# QFN44-2-DIP.net
KiCad netlist of a schematic drawn in EAGLE
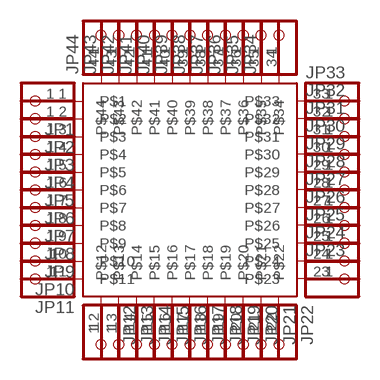
[diagram p0: schematic, sheet 1]

(export (version "E")
  (design (tool "Eeschema 10.0.6"))
  (components
    (comp (ref "JP1")
      (value "PINHD-1X1")
      (footprint "eagle-import:1X01")
      (libsource (lib "eagle-import") (part "PINHD-1X1"))
    )
    (comp (ref "JP2")
      (value "PINHD-1X1")
      (footprint "eagle-import:1X01")
      (libsource (lib "eagle-import") (part "PINHD-1X1"))
    )
    (comp (ref "JP3")
      (value "PINHD-1X1")
      (footprint "eagle-import:1X01")
      (libsource (lib "eagle-import") (part "PINHD-1X1"))
    )
    (comp (ref "JP4")
      (value "PINHD-1X1")
      (footprint "eagle-import:1X01")
      (libsource (lib "eagle-import") (part "PINHD-1X1"))
    )
    (comp (ref "JP5")
      (value "PINHD-1X1")
      (footprint "eagle-import:1X01")
      (libsource (lib "eagle-import") (part "PINHD-1X1"))
    )
    (comp (ref "JP6")
      (value "PINHD-1X1")
      (footprint "eagle-import:1X01")
      (libsource (lib "eagle-import") (part "PINHD-1X1"))
    )
    (comp (ref "JP7")
      (value "PINHD-1X1")
      (footprint "eagle-import:1X01")
      (libsource (lib "eagle-import") (part "PINHD-1X1"))
    )
    (comp (ref "JP8")
      (value "PINHD-1X1")
      (footprint "eagle-import:1X01")
      (libsource (lib "eagle-import") (part "PINHD-1X1"))
    )
    (comp (ref "JP9")
      (value "PINHD-1X1")
      (footprint "eagle-import:1X01")
      (libsource (lib "eagle-import") (part "PINHD-1X1"))
    )
    (comp (ref "JP10")
      (value "PINHD-1X1")
      (footprint "eagle-import:1X01")
      (libsource (lib "eagle-import") (part "PINHD-1X1"))
    )
    (comp (ref "JP11")
      (value "PINHD-1X1")
      (footprint "eagle-import:1X01")
      (libsource (lib "eagle-import") (part "PINHD-1X1"))
    )
    (comp (ref "JP12")
      (value "PINHD-1X1")
      (footprint "eagle-import:1X01")
      (libsource (lib "eagle-import") (part "PINHD-1X1"))
    )
    (comp (ref "JP13")
      (value "PINHD-1X1")
      (footprint "eagle-import:1X01")
      (libsource (lib "eagle-import") (part "PINHD-1X1"))
    )
    (comp (ref "JP14")
      (value "PINHD-1X1")
      (footprint "eagle-import:1X01")
      (libsource (lib "eagle-import") (part "PINHD-1X1"))
    )
    (comp (ref "JP15")
      (value "PINHD-1X1")
      (footprint "eagle-import:1X01")
      (libsource (lib "eagle-import") (part "PINHD-1X1"))
    )
    (comp (ref "JP16")
      (value "PINHD-1X1")
      (footprint "eagle-import:1X01")
      (libsource (lib "eagle-import") (part "PINHD-1X1"))
    )
    (comp (ref "JP17")
      (value "PINHD-1X1")
      (footprint "eagle-import:1X01")
      (libsource (lib "eagle-import") (part "PINHD-1X1"))
    )
    (comp (ref "JP18")
      (value "PINHD-1X1")
      (footprint "eagle-import:1X01")
      (libsource (lib "eagle-import") (part "PINHD-1X1"))
    )
    (comp (ref "JP19")
      (value "PINHD-1X1")
      (footprint "eagle-import:1X01")
      (libsource (lib "eagle-import") (part "PINHD-1X1"))
    )
    (comp (ref "JP20")
      (value "PINHD-1X1")
      (footprint "eagle-import:1X01")
      (libsource (lib "eagle-import") (part "PINHD-1X1"))
    )
    (comp (ref "JP21")
      (value "PINHD-1X1")
      (footprint "eagle-import:1X01")
      (libsource (lib "eagle-import") (part "PINHD-1X1"))
    )
    (comp (ref "JP22")
      (value "PINHD-1X1")
      (footprint "eagle-import:1X01")
      (libsource (lib "eagle-import") (part "PINHD-1X1"))
    )
    (comp (ref "JP23")
      (value "PINHD-1X1")
      (footprint "eagle-import:1X01")
      (libsource (lib "eagle-import") (part "PINHD-1X1"))
    )
    (comp (ref "JP24")
      (value "PINHD-1X1")
      (footprint "eagle-import:1X01")
      (libsource (lib "eagle-import") (part "PINHD-1X1"))
    )
    (comp (ref "JP25")
      (value "PINHD-1X1")
      (footprint "eagle-import:1X01")
      (libsource (lib "eagle-import") (part "PINHD-1X1"))
    )
    (comp (ref "JP26")
      (value "PINHD-1X1")
      (footprint "eagle-import:1X01")
      (libsource (lib "eagle-import") (part "PINHD-1X1"))
    )
    (comp (ref "JP27")
      (value "PINHD-1X1")
      (footprint "eagle-import:1X01")
      (libsource (lib "eagle-import") (part "PINHD-1X1"))
    )
    (comp (ref "JP28")
      (value "PINHD-1X1")
      (footprint "eagle-import:1X01")
      (libsource (lib "eagle-import") (part "PINHD-1X1"))
    )
    (comp (ref "JP29")
      (value "PINHD-1X1")
      (footprint "eagle-import:1X01")
      (libsource (lib "eagle-import") (part "PINHD-1X1"))
    )
    (comp (ref "JP30")
      (value "PINHD-1X1")
      (footprint "eagle-import:1X01")
      (libsource (lib "eagle-import") (part "PINHD-1X1"))
    )
    (comp (ref "JP31")
      (value "PINHD-1X1")
      (footprint "eagle-import:1X01")
      (libsource (lib "eagle-import") (part "PINHD-1X1"))
    )
    (comp (ref "JP32")
      (value "PINHD-1X1")
      (footprint "eagle-import:1X01")
      (libsource (lib "eagle-import") (part "PINHD-1X1"))
    )
    (comp (ref "JP33")
      (value "PINHD-1X1")
      (footprint "eagle-import:1X01")
      (libsource (lib "eagle-import") (part "PINHD-1X1"))
    )
    (comp (ref "JP34")
      (value "PINHD-1X1")
      (footprint "eagle-import:1X01")
      (libsource (lib "eagle-import") (part "PINHD-1X1"))
    )
    (comp (ref "JP35")
      (value "PINHD-1X1")
      (footprint "eagle-import:1X01")
      (libsource (lib "eagle-import") (part "PINHD-1X1"))
    )
    (comp (ref "JP36")
      (value "PINHD-1X1")
      (footprint "eagle-import:1X01")
      (libsource (lib "eagle-import") (part "PINHD-1X1"))
    )
    (comp (ref "JP37")
      (value "PINHD-1X1")
      (footprint "eagle-import:1X01")
      (libsource (lib "eagle-import") (part "PINHD-1X1"))
    )
    (comp (ref "JP38")
      (value "PINHD-1X1")
      (footprint "eagle-import:1X01")
      (libsource (lib "eagle-import") (part "PINHD-1X1"))
    )
    (comp (ref "JP39")
      (value "PINHD-1X1")
      (footprint "eagle-import:1X01")
      (libsource (lib "eagle-import") (part "PINHD-1X1"))
    )
    (comp (ref "JP40")
      (value "PINHD-1X1")
      (footprint "eagle-import:1X01")
      (libsource (lib "eagle-import") (part "PINHD-1X1"))
    )
    (comp (ref "JP41")
      (value "PINHD-1X1")
      (footprint "eagle-import:1X01")
      (libsource (lib "eagle-import") (part "PINHD-1X1"))
    )
    (comp (ref "JP42")
      (value "PINHD-1X1")
      (footprint "eagle-import:1X01")
      (libsource (lib "eagle-import") (part "PINHD-1X1"))
    )
    (comp (ref "JP43")
      (value "PINHD-1X1")
      (footprint "eagle-import:1X01")
      (libsource (lib "eagle-import") (part "PINHD-1X1"))
    )
    (comp (ref "JP44")
      (value "PINHD-1X1")
      (footprint "eagle-import:1X01")
      (libsource (lib "eagle-import") (part "PINHD-1X1"))
    )
    (comp (ref "U$1")
      (value "3M44")
      (footprint "eagle-import:3M44")
      (libsource (lib "eagle-import") (part "3M44"))
    )
  )
  (nets
    (net (code "1") (name "Net-(U$1-P$1)") (class "Default")
      (node (ref "JP1") (pin "1") (pinfunction "1_1") (pintype "passive"))
      (node (ref "U$1") (pin "1") (pinfunction "P$1_1") (pintype "bidirectional"))
    )
    (net (code "2") (name "Net-(U$1-P$2)") (class "Default")
      (node (ref "JP2") (pin "1") (pinfunction "1_1") (pintype "passive"))
      (node (ref "U$1") (pin "2") (pinfunction "P$2_2") (pintype "bidirectional"))
    )
    (net (code "3") (name "Net-(U$1-P$3)") (class "Default")
      (node (ref "JP3") (pin "1") (pinfunction "1_1") (pintype "passive"))
      (node (ref "U$1") (pin "3") (pinfunction "P$3_3") (pintype "bidirectional"))
    )
    (net (code "4") (name "Net-(U$1-P$4)") (class "Default")
      (node (ref "JP4") (pin "1") (pinfunction "1_1") (pintype "passive"))
      (node (ref "U$1") (pin "4") (pinfunction "P$4_4") (pintype "bidirectional"))
    )
    (net (code "5") (name "Net-(U$1-P$5)") (class "Default")
      (node (ref "JP5") (pin "1") (pinfunction "1_1") (pintype "passive"))
      (node (ref "U$1") (pin "5") (pinfunction "P$5_5") (pintype "bidirectional"))
    )
    (net (code "6") (name "Net-(U$1-P$6)") (class "Default")
      (node (ref "JP6") (pin "1") (pinfunction "1_1") (pintype "passive"))
      (node (ref "U$1") (pin "6") (pinfunction "P$6_6") (pintype "bidirectional"))
    )
    (net (code "7") (name "Net-(U$1-P$7)") (class "Default")
      (node (ref "JP7") (pin "1") (pinfunction "1_1") (pintype "passive"))
      (node (ref "U$1") (pin "7") (pinfunction "P$7_7") (pintype "bidirectional"))
    )
    (net (code "8") (name "Net-(U$1-P$8)") (class "Default")
      (node (ref "JP8") (pin "1") (pinfunction "1_1") (pintype "passive"))
      (node (ref "U$1") (pin "8") (pinfunction "P$8_8") (pintype "bidirectional"))
    )
    (net (code "9") (name "Net-(U$1-P$9)") (class "Default")
      (node (ref "JP9") (pin "1") (pinfunction "1_1") (pintype "passive"))
      (node (ref "U$1") (pin "9") (pinfunction "P$9_9") (pintype "bidirectional"))
    )
    (net (code "10") (name "Net-(U$1-P$10)") (class "Default")
      (node (ref "JP10") (pin "1") (pinfunction "1_1") (pintype "passive"))
      (node (ref "U$1") (pin "10") (pinfunction "P$10_10") (pintype "bidirectional"))
    )
    (net (code "11") (name "Net-(U$1-P$11)") (class "Default")
      (node (ref "JP11") (pin "1") (pinfunction "1_1") (pintype "passive"))
      (node (ref "U$1") (pin "11") (pinfunction "P$11_11") (pintype "bidirectional"))
    )
    (net (code "12") (name "Net-(U$1-P$12)") (class "Default")
      (node (ref "JP12") (pin "1") (pinfunction "1_1") (pintype "passive"))
      (node (ref "U$1") (pin "12") (pinfunction "P$12_12") (pintype "bidirectional"))
    )
    (net (code "13") (name "Net-(U$1-P$13)") (class "Default")
      (node (ref "JP13") (pin "1") (pinfunction "1_1") (pintype "passive"))
      (node (ref "U$1") (pin "13") (pinfunction "P$13_13") (pintype "bidirectional"))
    )
    (net (code "14") (name "Net-(U$1-P$14)") (class "Default")
      (node (ref "JP14") (pin "1") (pinfunction "1_1") (pintype "passive"))
      (node (ref "U$1") (pin "14") (pinfunction "P$14_14") (pintype "bidirectional"))
    )
    (net (code "15") (name "Net-(U$1-P$15)") (class "Default")
      (node (ref "JP15") (pin "1") (pinfunction "1_1") (pintype "passive"))
      (node (ref "U$1") (pin "15") (pinfunction "P$15_15") (pintype "bidirectional"))
    )
    (net (code "16") (name "Net-(U$1-P$16)") (class "Default")
      (node (ref "JP16") (pin "1") (pinfunction "1_1") (pintype "passive"))
      (node (ref "U$1") (pin "16") (pinfunction "P$16_16") (pintype "bidirectional"))
    )
    (net (code "17") (name "Net-(U$1-P$17)") (class "Default")
      (node (ref "JP17") (pin "1") (pinfunction "1_1") (pintype "passive"))
      (node (ref "U$1") (pin "17") (pinfunction "P$17_17") (pintype "bidirectional"))
    )
    (net (code "18") (name "Net-(U$1-P$18)") (class "Default")
      (node (ref "JP18") (pin "1") (pinfunction "1_1") (pintype "passive"))
      (node (ref "U$1") (pin "18") (pinfunction "P$18_18") (pintype "bidirectional"))
    )
    (net (code "19") (name "Net-(U$1-P$19)") (class "Default")
      (node (ref "JP19") (pin "1") (pinfunction "1_1") (pintype "passive"))
      (node (ref "U$1") (pin "19") (pinfunction "P$19_19") (pintype "bidirectional"))
    )
    (net (code "20") (name "Net-(U$1-P$20)") (class "Default")
      (node (ref "JP20") (pin "1") (pinfunction "1_1") (pintype "passive"))
      (node (ref "U$1") (pin "20") (pinfunction "P$20_20") (pintype "bidirectional"))
    )
    (net (code "21") (name "Net-(U$1-P$21)") (class "Default")
      (node (ref "JP21") (pin "1") (pinfunction "1_1") (pintype "passive"))
      (node (ref "U$1") (pin "21") (pinfunction "P$21_21") (pintype "bidirectional"))
    )
    (net (code "22") (name "Net-(U$1-P$22)") (class "Default")
      (node (ref "JP22") (pin "1") (pinfunction "1_1") (pintype "passive"))
      (node (ref "U$1") (pin "22") (pinfunction "P$22_22") (pintype "bidirectional"))
    )
    (net (code "23") (name "Net-(U$1-P$23)") (class "Default")
      (node (ref "JP23") (pin "1") (pinfunction "1_1") (pintype "passive"))
      (node (ref "U$1") (pin "23") (pinfunction "P$23_23") (pintype "bidirectional"))
    )
    (net (code "24") (name "Net-(U$1-P$24)") (class "Default")
      (node (ref "JP24") (pin "1") (pinfunction "1_1") (pintype "passive"))
      (node (ref "U$1") (pin "24") (pinfunction "P$24_24") (pintype "bidirectional"))
    )
    (net (code "25") (name "Net-(U$1-P$25)") (class "Default")
      (node (ref "JP25") (pin "1") (pinfunction "1_1") (pintype "passive"))
      (node (ref "U$1") (pin "25") (pinfunction "P$25_25") (pintype "bidirectional"))
    )
    (net (code "26") (name "Net-(U$1-P$26)") (class "Default")
      (node (ref "JP26") (pin "1") (pinfunction "1_1") (pintype "passive"))
      (node (ref "U$1") (pin "26") (pinfunction "P$26_26") (pintype "bidirectional"))
    )
    (net (code "27") (name "Net-(U$1-P$27)") (class "Default")
      (node (ref "JP27") (pin "1") (pinfunction "1_1") (pintype "passive"))
      (node (ref "U$1") (pin "27") (pinfunction "P$27_27") (pintype "bidirectional"))
    )
    (net (code "28") (name "Net-(U$1-P$28)") (class "Default")
      (node (ref "JP28") (pin "1") (pinfunction "1_1") (pintype "passive"))
      (node (ref "U$1") (pin "28") (pinfunction "P$28_28") (pintype "bidirectional"))
    )
    (net (code "29") (name "Net-(U$1-P$29)") (class "Default")
      (node (ref "JP29") (pin "1") (pinfunction "1_1") (pintype "passive"))
      (node (ref "U$1") (pin "29") (pinfunction "P$29_29") (pintype "bidirectional"))
    )
    (net (code "30") (name "Net-(U$1-P$30)") (class "Default")
      (node (ref "JP30") (pin "1") (pinfunction "1_1") (pintype "passive"))
      (node (ref "U$1") (pin "30") (pinfunction "P$30_30") (pintype "bidirectional"))
    )
    (net (code "31") (name "Net-(U$1-P$31)") (class "Default")
      (node (ref "JP31") (pin "1") (pinfunction "1_1") (pintype "passive"))
      (node (ref "U$1") (pin "31") (pinfunction "P$31_31") (pintype "bidirectional"))
    )
    (net (code "32") (name "Net-(U$1-P$32)") (class "Default")
      (node (ref "JP32") (pin "1") (pinfunction "1_1") (pintype "passive"))
      (node (ref "U$1") (pin "32") (pinfunction "P$32_32") (pintype "bidirectional"))
    )
    (net (code "33") (name "Net-(U$1-P$33)") (class "Default")
      (node (ref "JP33") (pin "1") (pinfunction "1_1") (pintype "passive"))
      (node (ref "U$1") (pin "33") (pinfunction "P$33_33") (pintype "bidirectional"))
    )
    (net (code "34") (name "Net-(U$1-P$34)") (class "Default")
      (node (ref "JP34") (pin "1") (pinfunction "1_1") (pintype "passive"))
      (node (ref "U$1") (pin "34") (pinfunction "P$34_34") (pintype "bidirectional"))
    )
    (net (code "35") (name "Net-(U$1-P$35)") (class "Default")
      (node (ref "JP35") (pin "1") (pinfunction "1_1") (pintype "passive"))
      (node (ref "U$1") (pin "35") (pinfunction "P$35_35") (pintype "bidirectional"))
    )
    (net (code "36") (name "Net-(U$1-P$36)") (class "Default")
      (node (ref "JP36") (pin "1") (pinfunction "1_1") (pintype "passive"))
      (node (ref "U$1") (pin "36") (pinfunction "P$36_36") (pintype "bidirectional"))
    )
    (net (code "37") (name "Net-(U$1-P$37)") (class "Default")
      (node (ref "JP37") (pin "1") (pinfunction "1_1") (pintype "passive"))
      (node (ref "U$1") (pin "37") (pinfunction "P$37_37") (pintype "bidirectional"))
    )
    (net (code "38") (name "Net-(U$1-P$38)") (class "Default")
      (node (ref "JP38") (pin "1") (pinfunction "1_1") (pintype "passive"))
      (node (ref "U$1") (pin "38") (pinfunction "P$38_38") (pintype "bidirectional"))
    )
    (net (code "39") (name "Net-(U$1-P$39)") (class "Default")
      (node (ref "JP39") (pin "1") (pinfunction "1_1") (pintype "passive"))
      (node (ref "U$1") (pin "39") (pinfunction "P$39_39") (pintype "bidirectional"))
    )
    (net (code "40") (name "Net-(U$1-P$40)") (class "Default")
      (node (ref "JP40") (pin "1") (pinfunction "1_1") (pintype "passive"))
      (node (ref "U$1") (pin "40") (pinfunction "P$40_40") (pintype "bidirectional"))
    )
    (net (code "41") (name "Net-(U$1-P$41)") (class "Default")
      (node (ref "JP41") (pin "1") (pinfunction "1_1") (pintype "passive"))
      (node (ref "U$1") (pin "41") (pinfunction "P$41_41") (pintype "bidirectional"))
    )
    (net (code "42") (name "Net-(U$1-P$42)") (class "Default")
      (node (ref "JP42") (pin "1") (pinfunction "1_1") (pintype "passive"))
      (node (ref "U$1") (pin "42") (pinfunction "P$42_42") (pintype "bidirectional"))
    )
    (net (code "43") (name "Net-(U$1-P$43)") (class "Default")
      (node (ref "JP43") (pin "1") (pinfunction "1_1") (pintype "passive"))
      (node (ref "U$1") (pin "43") (pinfunction "P$43_43") (pintype "bidirectional"))
    )
    (net (code "44") (name "Net-(U$1-P$44)") (class "Default")
      (node (ref "JP44") (pin "1") (pinfunction "1_1") (pintype "passive"))
      (node (ref "U$1") (pin "44") (pinfunction "P$44_44") (pintype "bidirectional"))
    )
  )
)
